# Power_Switch.net
KiCad netlist of a schematic drawn in Altium Designer
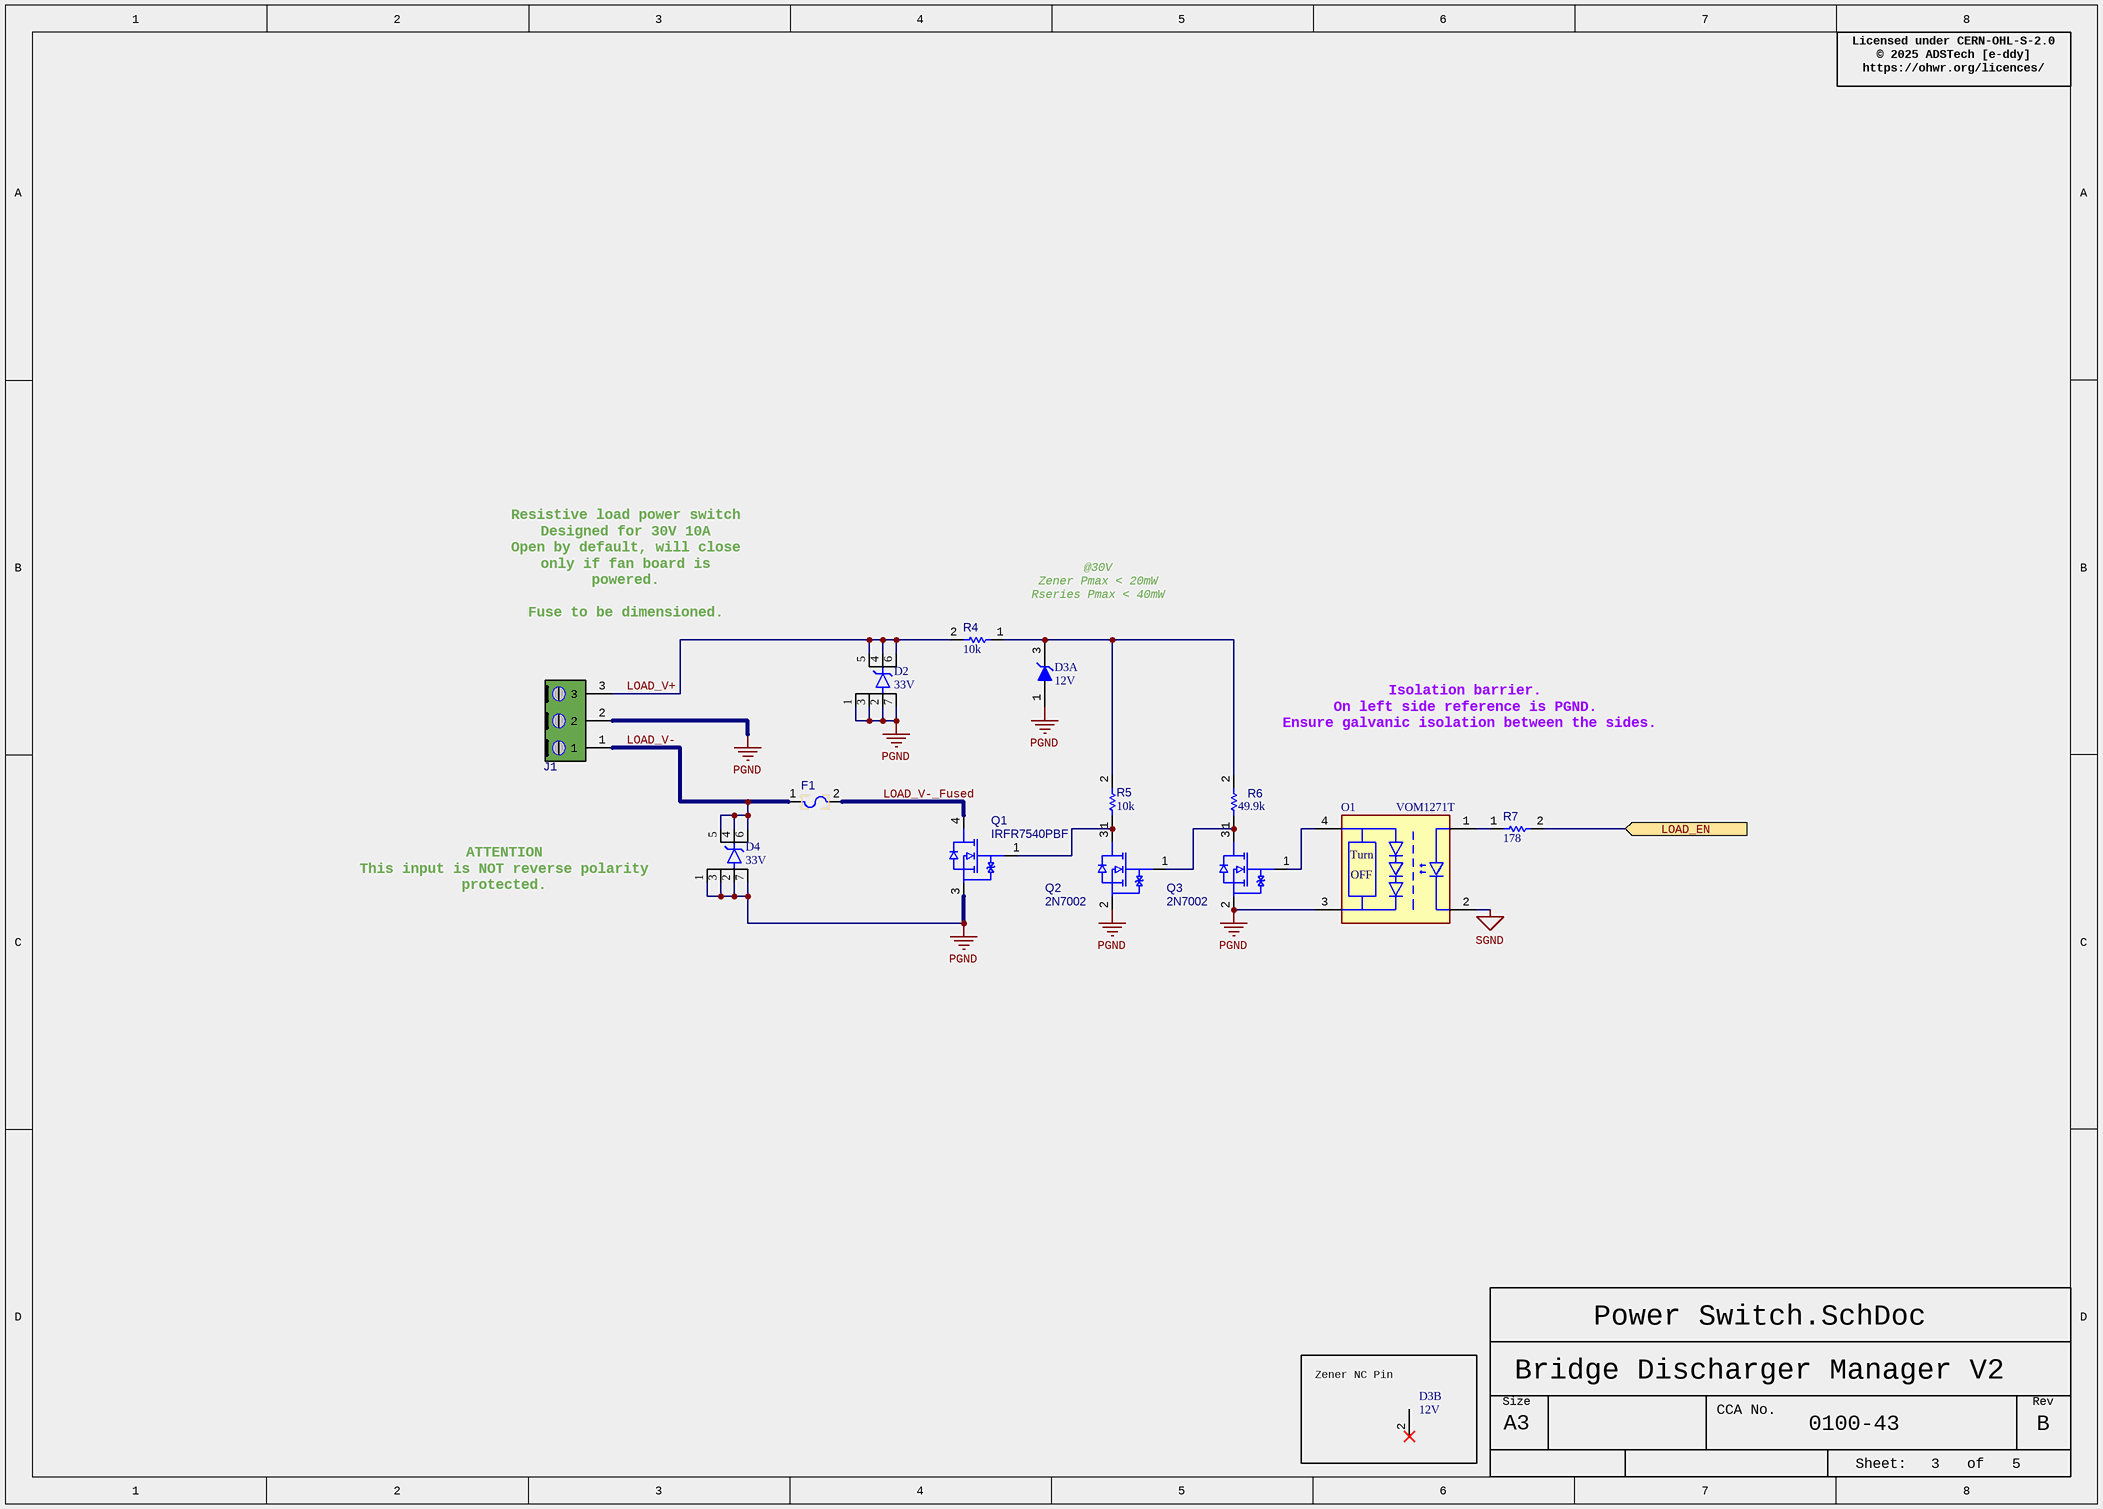
[diagram p0: Power Switch.SchDoc]

(export (version "E")
  (design (tool "Eeschema 10.0.6"))
  (components
    (comp (ref "D2")
      (value "33V")
      (footprint "FP-DRV0006A-MFG")
      (description "Trans Voltage Suppressor Diode, 33V V(RWM), Unidirectional, Silicon")
      (libsource (lib "FIME Lille") (part "05871d3186a2232acfb1f4d5e814824"))
    )
    (comp (ref "D3")
      (value "D-ZEN-12V-BZX84C12-7-F")
      (footprint "FP-SOT23-MFG")
      (description "Zener Diode, 12V V(Z), 5.39%, 0.35W, Silicon, Unidirectional")
      (fields (field (name "REFERENCE VOLTAGE-NOM") "12V"))
      (libsource (lib "FIME Lille") (part "4a6bcd6c75a58f30e1c7f5dd6419ea8"))
    )
    (comp (ref "D4")
      (value "33V")
      (footprint "FP-DRV0006A-MFG")
      (description "Trans Voltage Suppressor Diode, 33V V(RWM), Unidirectional, Silicon")
      (libsource (lib "FIME Lille") (part "05871d3186a2232acfb1f4d5e814824"))
    )
    (comp (ref "F1")
      (value "FUSE-HOLDER-Nanofuse")
      (footprint "FP-0155-MFG")
      (description "Fuses/Accessories")
      (libsource (lib "FIME Lille") (part "FUSE-HOLDER"))
    )
    (comp (ref "J1")
      (value "CON-TERM-3-5.08-30/12AWG")
      (footprint "TBJ05-03-1-G-G-Footprint-1")
      (description "Terminal Block, Wtb, 3POS, 30-12AWG;")
      (libsource (lib "FIME Lille") (part "TBJ05-03-1-G-G-Symbol-1"))
    )
    (comp (ref "O1")
      (value "VOM1271T")
      (footprint "IC-Optocoupler-VOM1271T-Footprint-1")
      (description "Buffer/Inverter Based MOSFET Driver, 0.000007A, PDSO4")
      (libsource (lib "FIME Lille") (part "VOM1271T"))
    )
    (comp (ref "Q1")
      (value "IRFR7540PBF")
      (footprint "FP-PG-TO252-3-MFG")
      (description "Power Field-Effect Transistor")
      (libsource (lib "FIME Lille") (part "dpak"))
    )
    (comp (ref "Q2")
      (value "2N7002")
      (footprint "FP-SOT23-MFG")
      (libsource (lib "FIME Lille") (part "Copy of CMP-00005-6"))
    )
    (comp (ref "Q3")
      (value "2N7002")
      (footprint "FP-SOT23-MFG")
      (libsource (lib "FIME Lille") (part "Copy of CMP-00005-6"))
    )
    (comp (ref "R4")
      (value "10k")
      (footprint "RES-0603-IPC_B")
      (description "0603 10000.0 Ω 1% 100ppm 0.1W Resistor")
      (fields (field (name "POWER") "100mW") (field (name "TOLERANCE") "1%"))
      (libsource (lib "FIME Lille") (part "RES-2"))
    )
    (comp (ref "R5")
      (value "10k")
      (footprint "RES-0603-IPC_B")
      (description "0603 10000.0 Ω 1% 100ppm 0.1W Resistor")
      (fields (field (name "POWER") "100mW") (field (name "TOLERANCE") "1%"))
      (libsource (lib "FIME Lille") (part "RES-2"))
    )
    (comp (ref "R6")
      (value "49.9k")
      (footprint "RES-0603-IPC_B")
      (description "0603 49900.0 Ω 1% 100ppm 0.1W Resistor")
      (fields (field (name "TOLERANCE") "1%") (field (name "MPN") "CRCW060349K9FKED"))
      (libsource (lib "FIME Lille") (part "RES-2"))
    )
    (comp (ref "R7")
      (value "178")
      (footprint "RES-0603-IPC_B")
      (description "0603 178.0 Ω 1% 100ppm 0.1W Resistor")
      (fields (field (name "POWER") "100mW") (field (name "MPN") "CRCW0603178RFKED"))
      (libsource (lib "FIME Lille") (part "RES-2"))
    )
  )
  (nets
    (net (code "1") (name "/LOAD_EN") (class "Default")
      (node (ref "R7") (pin "2") (pinfunction "2_2") (pintype "passive"))
    )
    (net (code "2") (name "/LOAD_V+") (class "Default")
      (node (ref "D2") (pin "4") (pinfunction "IN_4") (pintype "passive"))
      (node (ref "D2") (pin "5") (pinfunction "IN_5") (pintype "passive"))
      (node (ref "D2") (pin "6") (pinfunction "IN_6") (pintype "passive"))
      (node (ref "J1") (pin "3") (pinfunction "3_3") (pintype "passive"))
      (node (ref "R4") (pin "2") (pinfunction "2_2") (pintype "passive"))
    )
    (net (code "3") (name "/LOAD_V-") (class "Default")
      (node (ref "D4") (pin "4") (pinfunction "IN_4") (pintype "passive"))
      (node (ref "D4") (pin "5") (pinfunction "IN_5") (pintype "passive"))
      (node (ref "D4") (pin "6") (pinfunction "IN_6") (pintype "passive"))
      (node (ref "F1") (pin "1") (pinfunction "1_1") (pintype "passive"))
      (node (ref "J1") (pin "1") (pinfunction "1_1") (pintype "passive"))
    )
    (net (code "4") (name "/LOAD_V-_Fused") (class "Default")
      (node (ref "F1") (pin "2") (pinfunction "2_2") (pintype "passive"))
      (node (ref "Q1") (pin "4") (pinfunction "D_4") (pintype "passive"))
    )
    (net (code "5") (name "Net-(D3A-C)") (class "Default")
      (node (ref "D3") (pin "3") (pinfunction "C_3") (pintype "passive"))
      (node (ref "R4") (pin "1") (pinfunction "1_1") (pintype "passive"))
      (node (ref "R5") (pin "2") (pinfunction "2_2") (pintype "passive"))
      (node (ref "R6") (pin "2") (pinfunction "2_2") (pintype "passive"))
    )
    (net (code "6") (name "Net-(O1-A)") (class "Default")
      (node (ref "O1") (pin "1") (pinfunction "A_1") (pintype "passive"))
      (node (ref "R7") (pin "1") (pinfunction "1_1") (pintype "passive"))
    )
    (net (code "7") (name "Net-(O1-D)") (class "Default")
      (node (ref "O1") (pin "4") (pinfunction "D_4") (pintype "power_in"))
      (node (ref "Q3") (pin "1") (pinfunction "G_1") (pintype "passive"))
    )
    (net (code "8") (name "Net-(Q1-G)") (class "Default")
      (node (ref "Q1") (pin "1") (pinfunction "G_1") (pintype "passive"))
      (node (ref "Q2") (pin "3") (pinfunction "D_3") (pintype "passive"))
      (node (ref "R5") (pin "1") (pinfunction "1_1") (pintype "passive"))
    )
    (net (code "9") (name "Net-(Q2-G)") (class "Default")
      (node (ref "Q2") (pin "1") (pinfunction "G_1") (pintype "passive"))
      (node (ref "Q3") (pin "3") (pinfunction "D_3") (pintype "passive"))
      (node (ref "R6") (pin "1") (pinfunction "1_1") (pintype "passive"))
    )
    (net (code "10") (name "PGND") (class "Default")
      (node (ref "D2") (pin "1") (pinfunction "GND_1") (pintype "power_in"))
      (node (ref "D2") (pin "2") (pinfunction "GND_2") (pintype "power_in"))
      (node (ref "D2") (pin "3") (pinfunction "GND_3") (pintype "power_in"))
      (node (ref "D2") (pin "7") (pinfunction "GND_7") (pintype "power_in"))
      (node (ref "D3") (pin "1") (pinfunction "A_1") (pintype "passive"))
      (node (ref "D4") (pin "1") (pinfunction "GND_1") (pintype "power_in"))
      (node (ref "D4") (pin "2") (pinfunction "GND_2") (pintype "power_in"))
      (node (ref "D4") (pin "3") (pinfunction "GND_3") (pintype "power_in"))
      (node (ref "D4") (pin "7") (pinfunction "GND_7") (pintype "power_in"))
      (node (ref "J1") (pin "2") (pinfunction "2_2") (pintype "passive"))
      (node (ref "O1") (pin "3") (pinfunction "S_3") (pintype "passive"))
      (node (ref "Q1") (pin "3") (pinfunction "S_3") (pintype "passive"))
      (node (ref "Q2") (pin "2") (pinfunction "S_2") (pintype "passive"))
      (node (ref "Q3") (pin "2") (pinfunction "S_2") (pintype "passive"))
    )
    (net (code "11") (name "SGND") (class "Default")
      (node (ref "O1") (pin "2") (pinfunction "K_2") (pintype "passive"))
    )
    (net (code "12") (name "unconnected-(D3B-NC-Pad2)") (class "Default")
      (node (ref "D3") (pin "2") (pinfunction "NC_2") (pintype "passive+no_connect"))
    )
  )
)
